# Dashboard_buzzer_tester.net
KiCad netlist of a schematic drawn in EAGLE
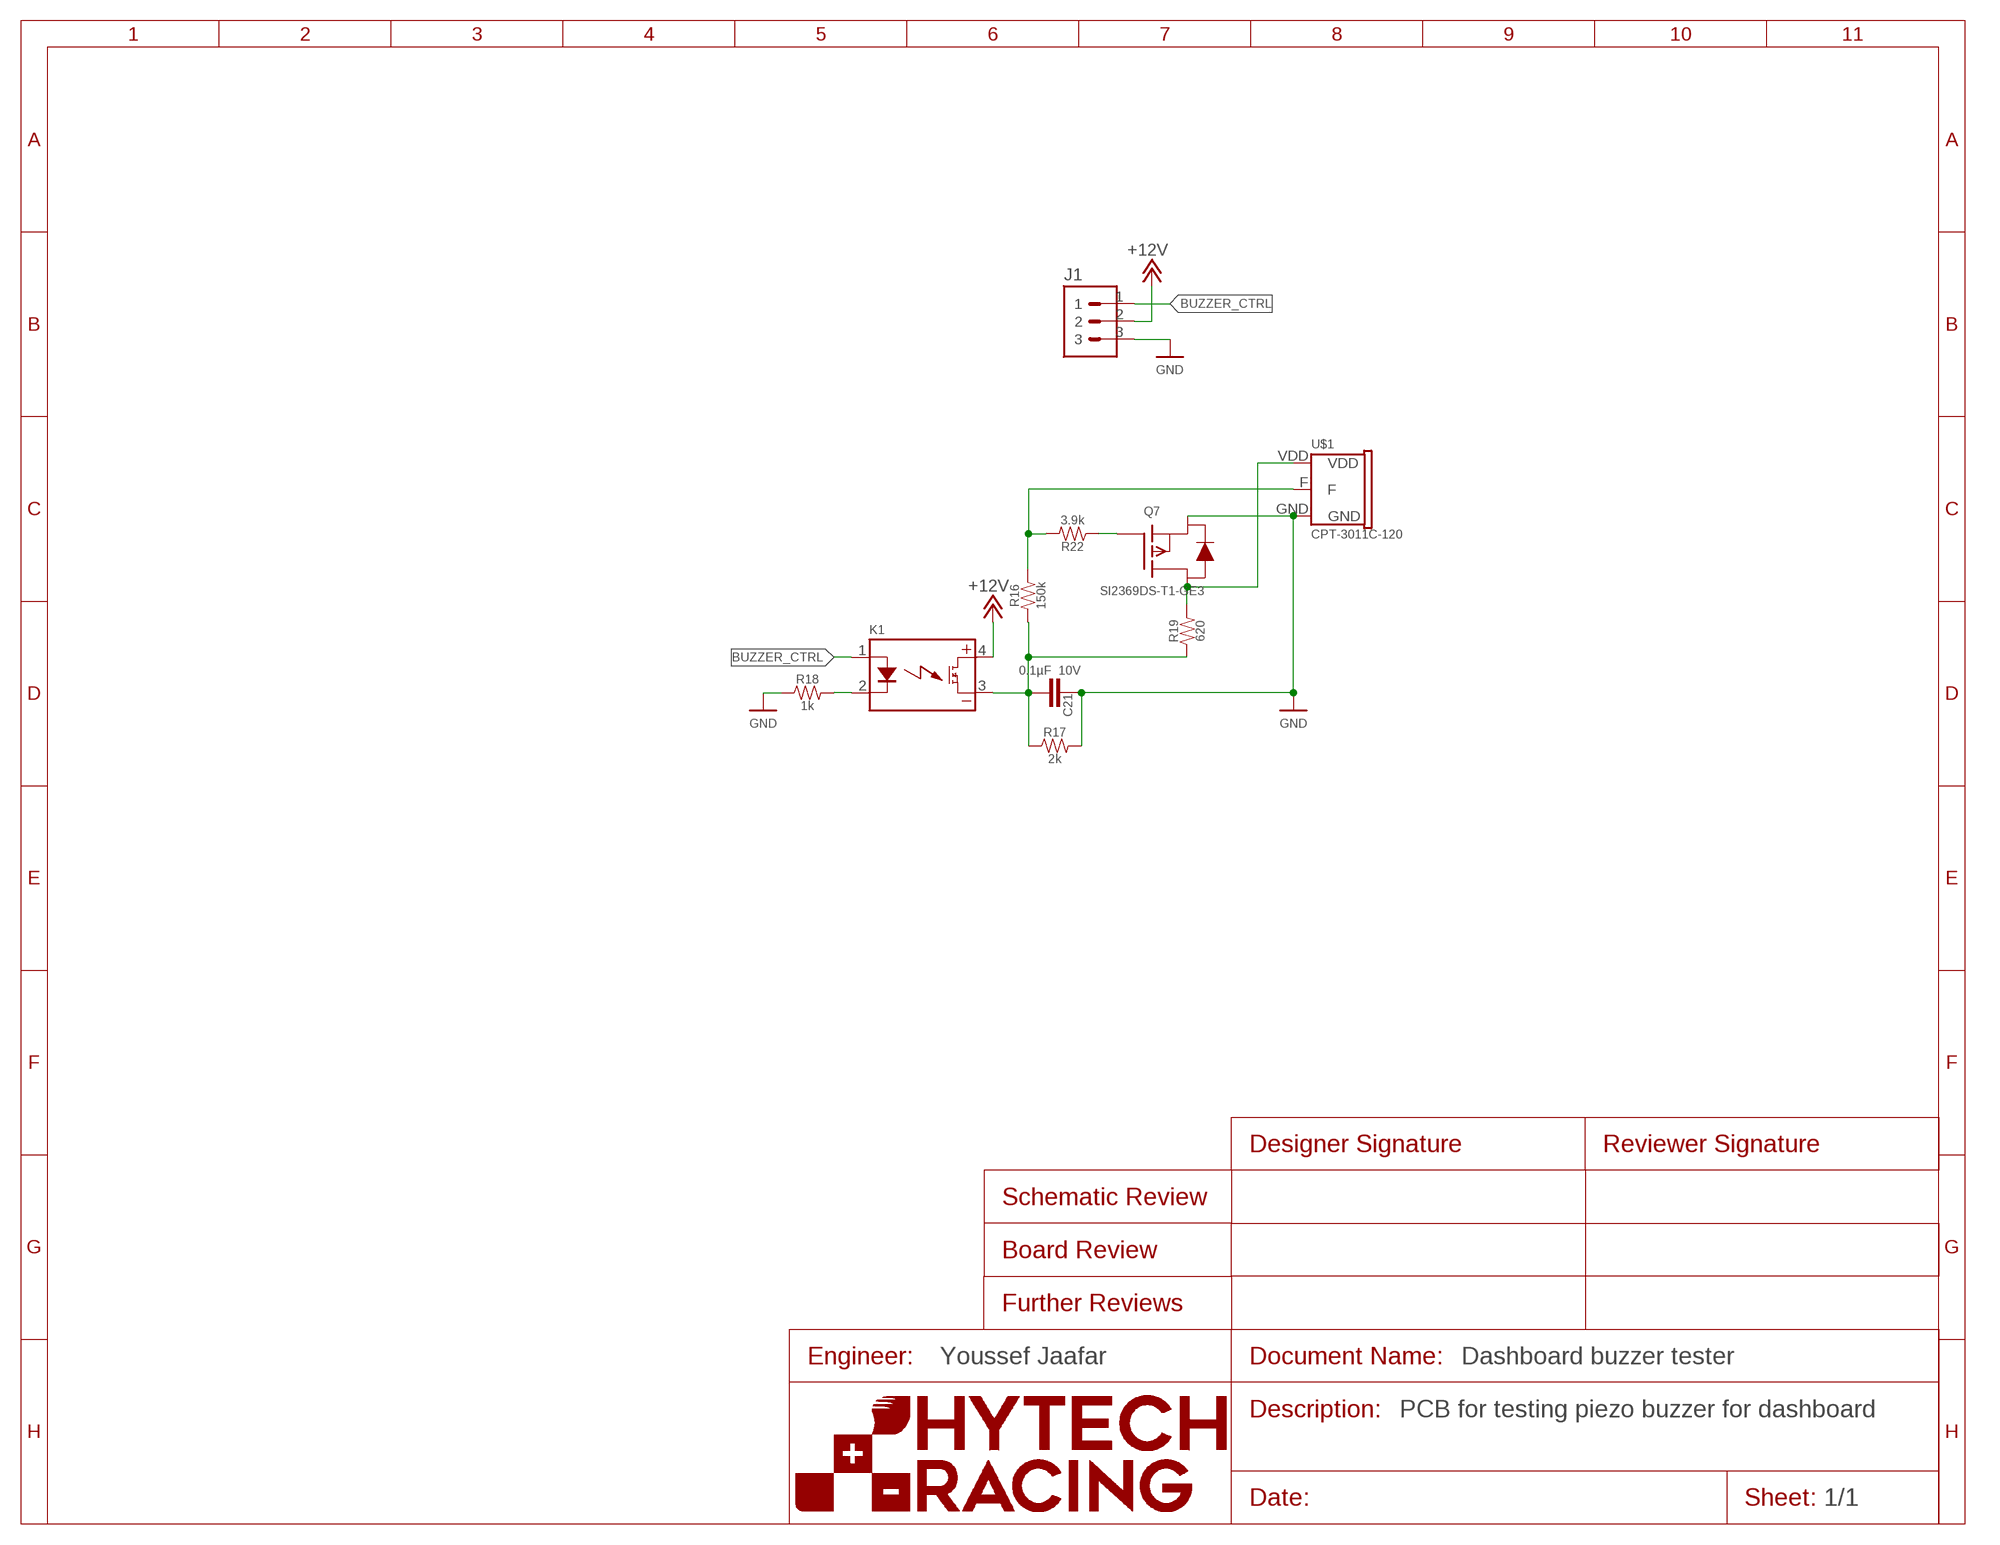
[diagram p0: schematic, sheet 1]

(export (version "E")
  (design (tool "Eeschema 10.0.6"))
  (components
    (comp (ref "C21")
      (value "CAPACITOR_0603_10V_0.1UF")
      (footprint "eagle-import:0603-CAP")
      (fields
        (field (name "CAPACITANCE") "0.1µF")
        (field (name "MANUFACTURER") "Vishay Vitramon")
        (field (name "MPN") "VJ0603Y104JXQPW1BC")
        (field (name "TOLERANCE") "5%")
        (field (name "VOLTAGE") "10V")
      )
      (libsource (lib "eagle-import") (part "CAPACITOR_?_060310V_0.1UF"))
    )
    (comp (ref "J1")
      (value "CONNECTOR-3")
      (footprint "eagle-import:1X03")
      (libsource (lib "eagle-import") (part "CONNECTOR-3"))
    )
    (comp (ref "K1")
      (value "CPC1002N")
      (footprint "eagle-import:SOP-04")
      (libsource (lib "eagle-import") (part "CPC1002N"))
    )
    (comp (ref "Q7")
      (value "TRANSISTOR_P_MOS_SOT23_SI2369DS-T1-GE3")
      (footprint "eagle-import:SOT-23")
      (fields (field (name "MANUFACTURER") "Vishay Siliconix") (field (name "MPN") "SI2369DS-T1-GE3"))
      (libsource (lib "eagle-import") (part "TRANSISTOR_P_MOS_?_SOT23SI2369DS-T1-GE3"))
    )
    (comp (ref "R16")
      (value "RESISTOR_0603_150K")
      (footprint "eagle-import:0603-RES")
      (fields
        (field (name "MANUFACTURER") "Panasonic Electronic Components")
        (field (name "MPN") "ERA-3AEB154V")
        (field (name "POWER") "0.1W")
        (field (name "RESISTANCE") "150k")
      )
      (libsource (lib "eagle-import") (part "RESISTOR_?_0603150K"))
    )
    (comp (ref "R17")
      (value "RESISTOR_0603_2K")
      (footprint "eagle-import:0603-RES")
      (fields
        (field (name "MANUFACTURER") "Panasonic Electronic Components")
        (field (name "MPN") "ERA-3ARB202V")
        (field (name "POWER") "0.1W")
        (field (name "RESISTANCE") "2k")
      )
      (libsource (lib "eagle-import") (part "RESISTOR_?_06032K"))
    )
    (comp (ref "R18")
      (value "RESISTOR_0603_1K")
      (footprint "eagle-import:0603-RES")
      (fields
        (field (name "MANUFACTURER") "Yageo")
        (field (name "MPN") "RC0603FR-071KL")
        (field (name "POWER") "0.1W")
        (field (name "RESISTANCE") "1k")
      )
      (libsource (lib "eagle-import") (part "RESISTOR_?_06031K"))
    )
    (comp (ref "R19")
      (value "RESISTOR_0603_620")
      (footprint "eagle-import:0603-RES")
      (fields
        (field (name "MANUFACTURER") "Yageo")
        (field (name "MPN") "RC0603FR-07620RL ")
        (field (name "POWER") "0.1W")
        (field (name "RESISTANCE") "620")
      )
      (libsource (lib "eagle-import") (part "RESISTOR_?_0603620"))
    )
    (comp (ref "R22")
      (value "RESISTOR_0603_3.9K")
      (footprint "eagle-import:0603-RES")
      (fields
        (field (name "MANUFACTURER") "Yageo")
        (field (name "MPN") "RC0603FR-073K9L")
        (field (name "POWER") "0.1W")
        (field (name "RESISTANCE") "3.9k")
      )
      (libsource (lib "eagle-import") (part "RESISTOR_?_06033.9K"))
    )
    (comp (ref "U$1")
      (value "BUZZER_3_PIN_CPT-3011C-120")
      (footprint "eagle-import:CPT-3011C-120")
      (fields
        (field (name "MANUFACTURER") "CUI Devices")
        (field (name "MPN") "CPT-3011C-120")
        (field (name "VOLTAGE") "12V")
      )
      (libsource (lib "eagle-import") (part "BUZZER_3_PIN_CPT-3011C-120"))
    )
  )
  (nets
    (net (code "1") (name "+12V") (class "Default")
      (node (ref "J1") (pin "2") (pinfunction "2_2") (pintype "passive"))
      (node (ref "K1") (pin "4") (pinfunction "DC+_4") (pintype "passive"))
    )
    (net (code "2") (name "BUZZER_CTRL") (class "Default")
      (node (ref "J1") (pin "1") (pinfunction "1_1") (pintype "passive"))
      (node (ref "K1") (pin "1") (pinfunction "CONTROL+_1") (pintype "passive"))
    )
    (net (code "3") (name "GND") (class "Default")
      (node (ref "C21") (pin "2") (pinfunction "2_2") (pintype "passive"))
      (node (ref "J1") (pin "3") (pinfunction "3_3") (pintype "passive"))
      (node (ref "Q7") (pin "2") (pinfunction "S_2") (pintype "passive"))
      (node (ref "R17") (pin "2") (pinfunction "2_2") (pintype "passive"))
      (node (ref "R18") (pin "1") (pinfunction "1_1") (pintype "passive"))
      (node (ref "U$1") (pin "GND") (pinfunction "GND_GND") (pintype "power_in"))
    )
    (net (code "4") (name "Net-(K1-CONTROL-)") (class "Default")
      (node (ref "K1") (pin "2") (pinfunction "CONTROL-_2") (pintype "passive"))
      (node (ref "R18") (pin "2") (pinfunction "2_2") (pintype "passive"))
    )
    (net (code "5") (name "Net-(K1-DC-)") (class "Default")
      (node (ref "C21") (pin "1") (pinfunction "1_1") (pintype "passive"))
      (node (ref "K1") (pin "3") (pinfunction "DC-_3") (pintype "passive"))
      (node (ref "R16") (pin "1") (pinfunction "1_1") (pintype "passive"))
      (node (ref "R17") (pin "1") (pinfunction "1_1") (pintype "passive"))
      (node (ref "R19") (pin "1") (pinfunction "1_1") (pintype "passive"))
    )
    (net (code "6") (name "Net-(Q7-D)") (class "Default")
      (node (ref "Q7") (pin "3") (pinfunction "D_3") (pintype "passive"))
      (node (ref "R19") (pin "2") (pinfunction "2_2") (pintype "passive"))
      (node (ref "U$1") (pin "VDD") (pinfunction "VDD_VDD") (pintype "power_in"))
    )
    (net (code "7") (name "Net-(Q7-G)") (class "Default")
      (node (ref "Q7") (pin "1") (pinfunction "G_1") (pintype "passive"))
      (node (ref "R22") (pin "1") (pinfunction "1_1") (pintype "passive"))
    )
    (net (code "8") (name "Net-(R16-Pad2)") (class "Default")
      (node (ref "R16") (pin "2") (pinfunction "2_2") (pintype "passive"))
      (node (ref "R22") (pin "2") (pinfunction "2_2") (pintype "passive"))
      (node (ref "U$1") (pin "F") (pinfunction "F_F") (pintype "bidirectional"))
    )
  )
)
